# paddle.net
KiCad netlist of a schematic drawn in EAGLE
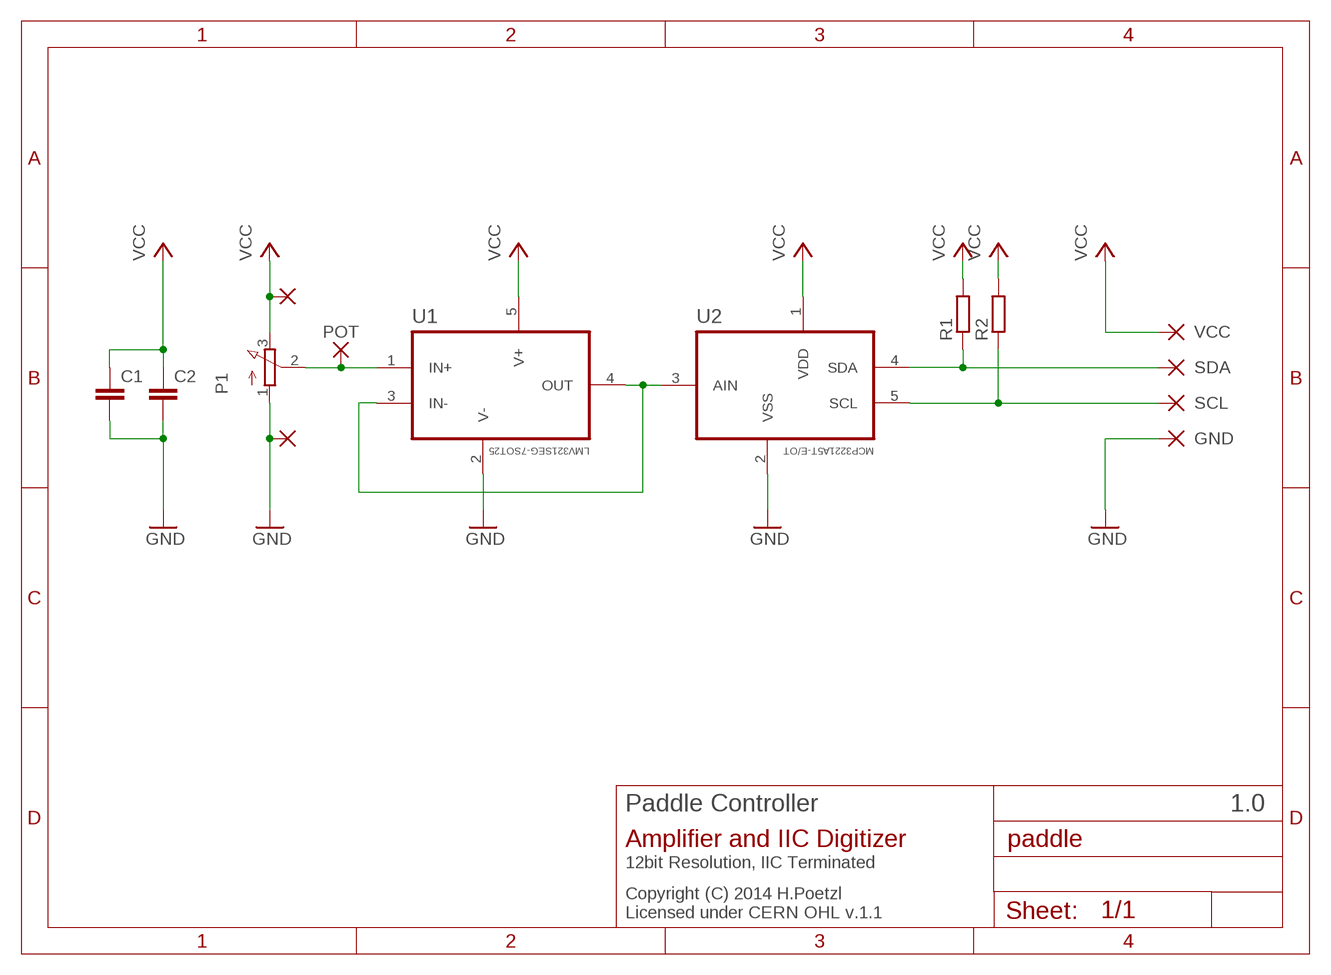
[diagram p0: schematic, sheet 1]

(export (version "E")
  (design (tool "Eeschema 10.0.6"))
  (components
    (comp (ref "C1")
      (value "C-EUC1206K")
      (footprint "eagle-import:C1206K")
      (libsource (lib "eagle-import") (part "C-EUC1206K"))
    )
    (comp (ref "C2")
      (value "C-EUC1206K")
      (footprint "eagle-import:C1206K")
      (libsource (lib "eagle-import") (part "C-EUC1206K"))
    )
    (comp (ref "GND")
      (value "SMD2")
      (footprint "eagle-import:SMD1,27-2,54")
      (libsource (lib "eagle-import") (part "SMD2"))
    )
    (comp (ref "P1")
      (value "3RP/1610N")
      (footprint "eagle-import:3RP_1610N")
      (libsource (lib "eagle-import") (part "3RP/1610N"))
    )
    (comp (ref "POT")
      (value "SMD2")
      (footprint "eagle-import:SMD1,27-2,54")
      (libsource (lib "eagle-import") (part "SMD2"))
    )
    (comp (ref "R1")
      (value "R-EU_0204/7")
      (footprint "eagle-import:0204_7")
      (libsource (lib "eagle-import") (part "R-EU_0204/7"))
    )
    (comp (ref "R2")
      (value "R-EU_0204/5")
      (footprint "eagle-import:0204_5")
      (libsource (lib "eagle-import") (part "R-EU_0204/5"))
    )
    (comp (ref "SCL")
      (value "SMD2")
      (footprint "eagle-import:SMD1,27-2,54")
      (libsource (lib "eagle-import") (part "SMD2"))
    )
    (comp (ref "SDA")
      (value "SMD2")
      (footprint "eagle-import:SMD1,27-2,54")
      (libsource (lib "eagle-import") (part "SMD2"))
    )
    (comp (ref "U1")
      (value "LMV321SEG-7SOT25")
      (footprint "eagle-import:SOT95P280X145-5N")
      (libsource (lib "eagle-import") (part "LMV321SEG-7SOT25"))
    )
    (comp (ref "U2")
      (value "MCP3221A5T-E/OT")
      (footprint "eagle-import:SOT95P270X145-5N")
      (libsource (lib "eagle-import") (part "MCP3221A5T-E/OT"))
    )
    (comp (ref "VCC")
      (value "SMD2")
      (footprint "eagle-import:SMD1,27-2,54")
      (libsource (lib "eagle-import") (part "SMD2"))
    )
    (comp (ref "VCC1")
      (value "SMD2")
      (footprint "eagle-import:SMD1,27-2,54")
      (libsource (lib "eagle-import") (part "SMD2"))
    )
    (comp (ref "VCC2")
      (value "SMD2")
      (footprint "eagle-import:SMD1,27-2,54")
      (libsource (lib "eagle-import") (part "SMD2"))
    )
  )
  (nets
    (net (code "1") (name "GND") (class "Default")
      (node (ref "C1") (pin "2") (pinfunction "2_2") (pintype "passive"))
      (node (ref "C2") (pin "2") (pinfunction "2_2") (pintype "passive"))
      (node (ref "GND") (pin "1") (pinfunction "P_1") (pintype "passive"))
      (node (ref "P1") (pin "1") (pinfunction "A_1") (pintype "passive"))
      (node (ref "U1") (pin "2") (pinfunction "V-_2") (pintype "power_in"))
      (node (ref "U2") (pin "2") (pinfunction "VSS_2") (pintype "passive"))
      (node (ref "VCC2") (pin "1") (pinfunction "P_1") (pintype "passive"))
    )
    (net (code "2") (name "Net-(P1-S)") (class "Default")
      (node (ref "P1") (pin "2") (pinfunction "S_2") (pintype "passive"))
      (node (ref "POT") (pin "1") (pinfunction "P_1") (pintype "passive"))
      (node (ref "U1") (pin "1") (pinfunction "IN+_1") (pintype "input"))
    )
    (net (code "3") (name "Net-(SCL-P)") (class "Default")
      (node (ref "R2") (pin "1") (pinfunction "1_1") (pintype "passive"))
      (node (ref "SCL") (pin "1") (pinfunction "P_1") (pintype "passive"))
      (node (ref "U2") (pin "5") (pinfunction "SCL_5") (pintype "input"))
    )
    (net (code "4") (name "Net-(SDA-P)") (class "Default")
      (node (ref "R1") (pin "1") (pinfunction "1_1") (pintype "passive"))
      (node (ref "SDA") (pin "1") (pinfunction "P_1") (pintype "passive"))
      (node (ref "U2") (pin "4") (pinfunction "SDA_4") (pintype "bidirectional"))
    )
    (net (code "5") (name "Net-(U1-IN-)") (class "Default")
      (node (ref "U1") (pin "3") (pinfunction "IN-_3") (pintype "input"))
      (node (ref "U1") (pin "4") (pinfunction "OUT_4") (pintype "output"))
      (node (ref "U2") (pin "3") (pinfunction "AIN_3") (pintype "input"))
    )
    (net (code "6") (name "VCC") (class "Default")
      (node (ref "C1") (pin "1") (pinfunction "1_1") (pintype "passive"))
      (node (ref "C2") (pin "1") (pinfunction "1_1") (pintype "passive"))
      (node (ref "P1") (pin "3") (pinfunction "E_3") (pintype "passive"))
      (node (ref "R1") (pin "2") (pinfunction "2_2") (pintype "passive"))
      (node (ref "R2") (pin "2") (pinfunction "2_2") (pintype "passive"))
      (node (ref "U1") (pin "5") (pinfunction "V+_5") (pintype "power_in"))
      (node (ref "U2") (pin "1") (pinfunction "VDD_1") (pintype "power_in"))
      (node (ref "VCC") (pin "1") (pinfunction "P_1") (pintype "passive"))
      (node (ref "VCC1") (pin "1") (pinfunction "P_1") (pintype "passive"))
    )
  )
)
